# Connectors.net
KiCad netlist of a schematic drawn in Altium Designer
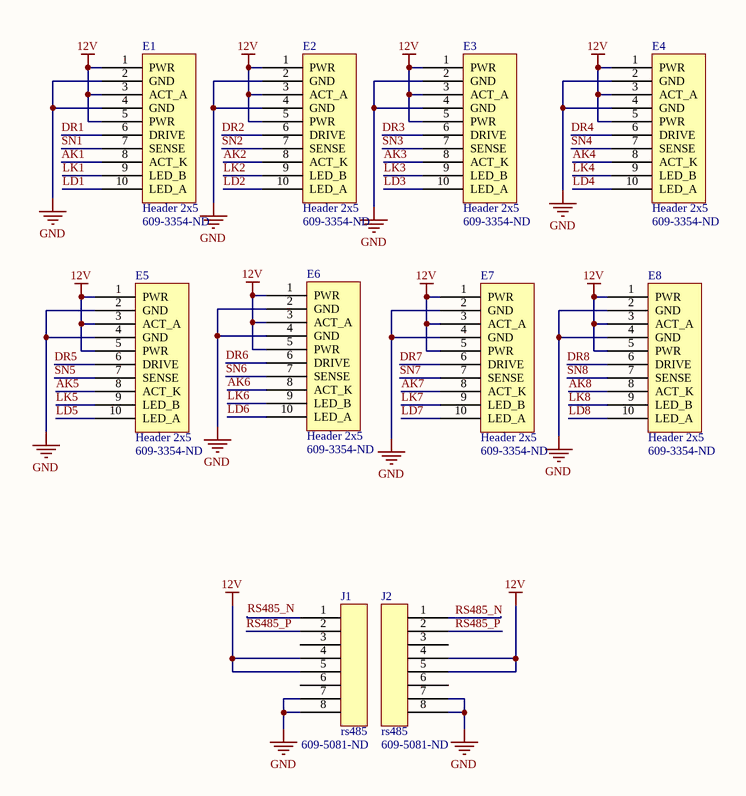
[diagram p0: Connectors.SchDoc]

(export (version "E")
  (design (tool "Eeschema 10.0.6"))
  (components
    (comp (ref "E1")
      (value "Header 2x5")
      (footprint "2x5")
      (description "Header")
      (fields (field (name "SUPPLIER PART NUMBER 1") "609-3354-ND"))
      (libsource (lib "ToolDoorController") (part "Header 2x5a"))
    )
    (comp (ref "E2")
      (value "Header 2x5")
      (footprint "2x5")
      (description "Header")
      (fields (field (name "SUPPLIER PART NUMBER 1") "609-3354-ND"))
      (libsource (lib "ToolDoorController") (part "Header 2x5a"))
    )
    (comp (ref "E3")
      (value "Header 2x5")
      (footprint "2x5")
      (description "Header")
      (fields (field (name "SUPPLIER PART NUMBER 1") "609-3354-ND"))
      (libsource (lib "ToolDoorController") (part "Header 2x5a"))
    )
    (comp (ref "E4")
      (value "Header 2x5")
      (footprint "2x5")
      (description "Header")
      (fields (field (name "SUPPLIER PART NUMBER 1") "609-3354-ND"))
      (libsource (lib "ToolDoorController") (part "Header 2x5a"))
    )
    (comp (ref "E5")
      (value "Header 2x5")
      (footprint "2x5")
      (description "Header")
      (fields (field (name "SUPPLIER PART NUMBER 1") "609-3354-ND"))
      (libsource (lib "ToolDoorController") (part "Header 2x5a"))
    )
    (comp (ref "E6")
      (value "Header 2x5")
      (footprint "2x5")
      (description "Header")
      (fields (field (name "SUPPLIER PART NUMBER 1") "609-3354-ND"))
      (libsource (lib "ToolDoorController") (part "Header 2x5a"))
    )
    (comp (ref "E7")
      (value "Header 2x5")
      (footprint "2x5")
      (description "Header")
      (fields (field (name "SUPPLIER PART NUMBER 1") "609-3354-ND"))
      (libsource (lib "ToolDoorController") (part "Header 2x5a"))
    )
    (comp (ref "E8")
      (value "Header 2x5")
      (footprint "2x5")
      (description "Header")
      (fields (field (name "SUPPLIER PART NUMBER 1") "609-3354-ND"))
      (libsource (lib "ToolDoorController") (part "Header 2x5a"))
    )
    (comp (ref "J1")
      (value "rs485")
      (footprint "RJ45")
      (description "rj45")
      (fields (field (name "SUPPLIER PART NUMBER 1") "609-5081-ND"))
      (libsource (lib "ToolDoorController") (part "rj45"))
    )
    (comp (ref "J2")
      (value "rs485")
      (footprint "RJ45")
      (description "rj45")
      (fields (field (name "SUPPLIER PART NUMBER 1") "609-5081-ND"))
      (libsource (lib "") (part "rj45_1"))
    )
  )
  (nets
    (net (code "1") (name "/AK1") (class "Default")
      (node (ref "E1") (pin "8") (pinfunction "ACT_K_8") (pintype "power_in"))
    )
    (net (code "2") (name "/AK2") (class "Default")
      (node (ref "E2") (pin "8") (pinfunction "ACT_K_8") (pintype "power_in"))
    )
    (net (code "3") (name "/AK3") (class "Default")
      (node (ref "E3") (pin "8") (pinfunction "ACT_K_8") (pintype "power_in"))
    )
    (net (code "4") (name "/AK4") (class "Default")
      (node (ref "E4") (pin "8") (pinfunction "ACT_K_8") (pintype "power_in"))
    )
    (net (code "5") (name "/AK5") (class "Default")
      (node (ref "E5") (pin "8") (pinfunction "ACT_K_8") (pintype "power_in"))
    )
    (net (code "6") (name "/AK6") (class "Default")
      (node (ref "E6") (pin "8") (pinfunction "ACT_K_8") (pintype "power_in"))
    )
    (net (code "7") (name "/AK7") (class "Default")
      (node (ref "E7") (pin "8") (pinfunction "ACT_K_8") (pintype "power_in"))
    )
    (net (code "8") (name "/AK8") (class "Default")
      (node (ref "E8") (pin "8") (pinfunction "ACT_K_8") (pintype "power_in"))
    )
    (net (code "9") (name "/DR1") (class "Default")
      (node (ref "E1") (pin "6") (pinfunction "DRIVE_6") (pintype "power_in"))
    )
    (net (code "10") (name "/DR2") (class "Default")
      (node (ref "E2") (pin "6") (pinfunction "DRIVE_6") (pintype "power_in"))
    )
    (net (code "11") (name "/DR3") (class "Default")
      (node (ref "E3") (pin "6") (pinfunction "DRIVE_6") (pintype "power_in"))
    )
    (net (code "12") (name "/DR4") (class "Default")
      (node (ref "E4") (pin "6") (pinfunction "DRIVE_6") (pintype "power_in"))
    )
    (net (code "13") (name "/DR5") (class "Default")
      (node (ref "E5") (pin "6") (pinfunction "DRIVE_6") (pintype "power_in"))
    )
    (net (code "14") (name "/DR6") (class "Default")
      (node (ref "E6") (pin "6") (pinfunction "DRIVE_6") (pintype "power_in"))
    )
    (net (code "15") (name "/DR7") (class "Default")
      (node (ref "E7") (pin "6") (pinfunction "DRIVE_6") (pintype "power_in"))
    )
    (net (code "16") (name "/DR8") (class "Default")
      (node (ref "E8") (pin "6") (pinfunction "DRIVE_6") (pintype "power_in"))
    )
    (net (code "17") (name "/LD1") (class "Default")
      (node (ref "E1") (pin "10") (pinfunction "LED_A_10") (pintype "power_in"))
    )
    (net (code "18") (name "/LD2") (class "Default")
      (node (ref "E2") (pin "10") (pinfunction "LED_A_10") (pintype "power_in"))
    )
    (net (code "19") (name "/LD3") (class "Default")
      (node (ref "E3") (pin "10") (pinfunction "LED_A_10") (pintype "power_in"))
    )
    (net (code "20") (name "/LD4") (class "Default")
      (node (ref "E4") (pin "10") (pinfunction "LED_A_10") (pintype "power_in"))
    )
    (net (code "21") (name "/LD5") (class "Default")
      (node (ref "E5") (pin "10") (pinfunction "LED_A_10") (pintype "power_in"))
    )
    (net (code "22") (name "/LD6") (class "Default")
      (node (ref "E6") (pin "10") (pinfunction "LED_A_10") (pintype "power_in"))
    )
    (net (code "23") (name "/LD7") (class "Default")
      (node (ref "E7") (pin "10") (pinfunction "LED_A_10") (pintype "power_in"))
    )
    (net (code "24") (name "/LD8") (class "Default")
      (node (ref "E8") (pin "10") (pinfunction "LED_A_10") (pintype "power_in"))
    )
    (net (code "25") (name "/LK1") (class "Default")
      (node (ref "E1") (pin "9") (pinfunction "LED_B_9") (pintype "power_in"))
    )
    (net (code "26") (name "/LK2") (class "Default")
      (node (ref "E2") (pin "9") (pinfunction "LED_B_9") (pintype "power_in"))
    )
    (net (code "27") (name "/LK3") (class "Default")
      (node (ref "E3") (pin "9") (pinfunction "LED_B_9") (pintype "power_in"))
    )
    (net (code "28") (name "/LK4") (class "Default")
      (node (ref "E4") (pin "9") (pinfunction "LED_B_9") (pintype "power_in"))
    )
    (net (code "29") (name "/LK5") (class "Default")
      (node (ref "E5") (pin "9") (pinfunction "LED_B_9") (pintype "power_in"))
    )
    (net (code "30") (name "/LK6") (class "Default")
      (node (ref "E6") (pin "9") (pinfunction "LED_B_9") (pintype "power_in"))
    )
    (net (code "31") (name "/LK7") (class "Default")
      (node (ref "E7") (pin "9") (pinfunction "LED_B_9") (pintype "power_in"))
    )
    (net (code "32") (name "/LK8") (class "Default")
      (node (ref "E8") (pin "9") (pinfunction "LED_B_9") (pintype "power_in"))
    )
    (net (code "33") (name "/RS485_N") (class "Default")
      (node (ref "J1") (pin "1") (pinfunction "1_1") (pintype "power_in"))
      (node (ref "J2") (pin "1") (pinfunction "1_1") (pintype "power_in"))
    )
    (net (code "34") (name "/RS485_P") (class "Default")
      (node (ref "J1") (pin "2") (pinfunction "2_2") (pintype "power_in"))
      (node (ref "J2") (pin "2") (pinfunction "2_2") (pintype "power_in"))
    )
    (net (code "35") (name "/SN1") (class "Default")
      (node (ref "E1") (pin "7") (pinfunction "SENSE_7") (pintype "power_in"))
    )
    (net (code "36") (name "/SN2") (class "Default")
      (node (ref "E2") (pin "7") (pinfunction "SENSE_7") (pintype "power_in"))
    )
    (net (code "37") (name "/SN3") (class "Default")
      (node (ref "E3") (pin "7") (pinfunction "SENSE_7") (pintype "power_in"))
    )
    (net (code "38") (name "/SN4") (class "Default")
      (node (ref "E4") (pin "7") (pinfunction "SENSE_7") (pintype "power_in"))
    )
    (net (code "39") (name "/SN5") (class "Default")
      (node (ref "E5") (pin "7") (pinfunction "SENSE_7") (pintype "power_in"))
    )
    (net (code "40") (name "/SN6") (class "Default")
      (node (ref "E6") (pin "7") (pinfunction "SENSE_7") (pintype "power_in"))
    )
    (net (code "41") (name "/SN7") (class "Default")
      (node (ref "E7") (pin "7") (pinfunction "SENSE_7") (pintype "power_in"))
    )
    (net (code "42") (name "/SN8") (class "Default")
      (node (ref "E8") (pin "7") (pinfunction "SENSE_7") (pintype "power_in"))
    )
    (net (code "43") (name "12V") (class "Default")
      (node (ref "E1") (pin "1") (pinfunction "PWR_1") (pintype "power_in"))
      (node (ref "E1") (pin "3") (pinfunction "ACT_A_3") (pintype "power_in"))
      (node (ref "E1") (pin "5") (pinfunction "PWR_5") (pintype "power_in"))
      (node (ref "E2") (pin "1") (pinfunction "PWR_1") (pintype "power_in"))
      (node (ref "E2") (pin "3") (pinfunction "ACT_A_3") (pintype "power_in"))
      (node (ref "E2") (pin "5") (pinfunction "PWR_5") (pintype "power_in"))
      (node (ref "E3") (pin "1") (pinfunction "PWR_1") (pintype "power_in"))
      (node (ref "E3") (pin "3") (pinfunction "ACT_A_3") (pintype "power_in"))
      (node (ref "E3") (pin "5") (pinfunction "PWR_5") (pintype "power_in"))
      (node (ref "E4") (pin "1") (pinfunction "PWR_1") (pintype "power_in"))
      (node (ref "E4") (pin "3") (pinfunction "ACT_A_3") (pintype "power_in"))
      (node (ref "E4") (pin "5") (pinfunction "PWR_5") (pintype "power_in"))
      (node (ref "E5") (pin "1") (pinfunction "PWR_1") (pintype "power_in"))
      (node (ref "E5") (pin "3") (pinfunction "ACT_A_3") (pintype "power_in"))
      (node (ref "E5") (pin "5") (pinfunction "PWR_5") (pintype "power_in"))
      (node (ref "E6") (pin "1") (pinfunction "PWR_1") (pintype "power_in"))
      (node (ref "E6") (pin "3") (pinfunction "ACT_A_3") (pintype "power_in"))
      (node (ref "E6") (pin "5") (pinfunction "PWR_5") (pintype "power_in"))
      (node (ref "E7") (pin "1") (pinfunction "PWR_1") (pintype "power_in"))
      (node (ref "E7") (pin "3") (pinfunction "ACT_A_3") (pintype "power_in"))
      (node (ref "E7") (pin "5") (pinfunction "PWR_5") (pintype "power_in"))
      (node (ref "E8") (pin "1") (pinfunction "PWR_1") (pintype "power_in"))
      (node (ref "E8") (pin "3") (pinfunction "ACT_A_3") (pintype "power_in"))
      (node (ref "E8") (pin "5") (pinfunction "PWR_5") (pintype "power_in"))
      (node (ref "J1") (pin "4") (pinfunction "4_4") (pintype "power_in"))
      (node (ref "J1") (pin "5") (pinfunction "5_5") (pintype "power_in"))
      (node (ref "J2") (pin "4") (pinfunction "4_4") (pintype "power_in"))
      (node (ref "J2") (pin "5") (pinfunction "5_5") (pintype "power_in"))
    )
    (net (code "44") (name "GND") (class "Default")
      (node (ref "E1") (pin "2") (pinfunction "GND_2") (pintype "power_in"))
      (node (ref "E1") (pin "4") (pinfunction "GND_4") (pintype "power_in"))
      (node (ref "E2") (pin "2") (pinfunction "GND_2") (pintype "power_in"))
      (node (ref "E2") (pin "4") (pinfunction "GND_4") (pintype "power_in"))
      (node (ref "E3") (pin "2") (pinfunction "GND_2") (pintype "power_in"))
      (node (ref "E3") (pin "4") (pinfunction "GND_4") (pintype "power_in"))
      (node (ref "E4") (pin "2") (pinfunction "GND_2") (pintype "power_in"))
      (node (ref "E4") (pin "4") (pinfunction "GND_4") (pintype "power_in"))
      (node (ref "E5") (pin "2") (pinfunction "GND_2") (pintype "power_in"))
      (node (ref "E5") (pin "4") (pinfunction "GND_4") (pintype "power_in"))
      (node (ref "E6") (pin "2") (pinfunction "GND_2") (pintype "power_in"))
      (node (ref "E6") (pin "4") (pinfunction "GND_4") (pintype "power_in"))
      (node (ref "E7") (pin "2") (pinfunction "GND_2") (pintype "power_in"))
      (node (ref "E7") (pin "4") (pinfunction "GND_4") (pintype "power_in"))
      (node (ref "E8") (pin "2") (pinfunction "GND_2") (pintype "power_in"))
      (node (ref "E8") (pin "4") (pinfunction "GND_4") (pintype "power_in"))
      (node (ref "J1") (pin "7") (pinfunction "7_7") (pintype "power_in"))
      (node (ref "J1") (pin "8") (pinfunction "8_8") (pintype "power_in"))
      (node (ref "J2") (pin "7") (pinfunction "7_7") (pintype "power_in"))
      (node (ref "J2") (pin "8") (pinfunction "8_8") (pintype "power_in"))
    )
    (net (code "45") (name "unconnected-(J1-Pad3)") (class "Default")
      (node (ref "J1") (pin "3") (pinfunction "3_3") (pintype "power_in"))
    )
    (net (code "46") (name "unconnected-(J1-Pad6)") (class "Default")
      (node (ref "J1") (pin "6") (pinfunction "6_6") (pintype "power_in"))
    )
    (net (code "47") (name "unconnected-(J2-Pad3)") (class "Default")
      (node (ref "J2") (pin "3") (pinfunction "3_3") (pintype "power_in"))
    )
    (net (code "48") (name "unconnected-(J2-Pad6)") (class "Default")
      (node (ref "J2") (pin "6") (pinfunction "6_6") (pintype "power_in"))
    )
  )
)
